# ESP32_S3.net
KiCad netlist of a schematic drawn in Altium Designer
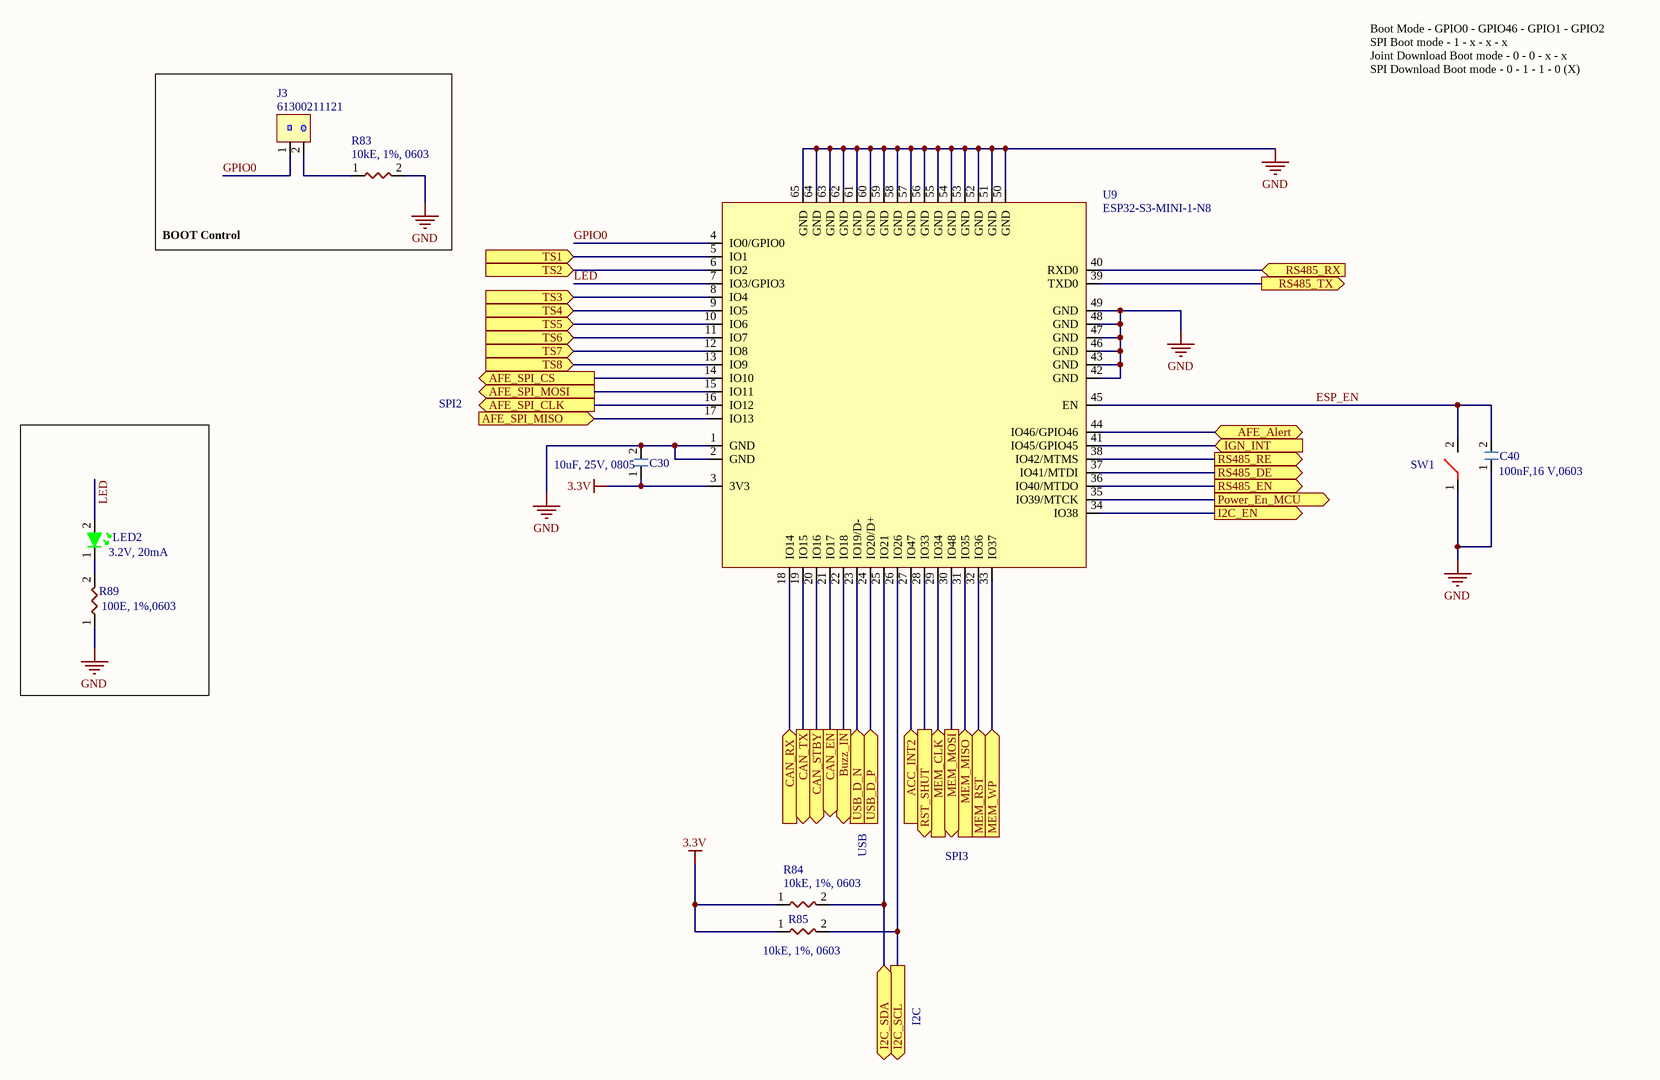
[diagram p0: ESP32_S3.SchDoc]

(export (version "E")
  (design (tool "Eeschema 10.0.6"))
  (components
    (comp (ref "C30")
      (value "GRM21BZ71E106KE15L")
      (footprint "BMS_V2.1_Adv:CAPC2012X13N 0805")
      (description "Multilayer Ceramic Capacitor, 10 uF, 25V, ±10%,  X7R 0805 (2012 Metric)")
      (fields
        (field (name "MANUFACTURER") "Murata")
        (field (name "TOLERANCE") "10%")
        (field (name "VALUE DISPLAY") "10uF, 25V, 0805")
      )
      (libsource (lib "BMS_V2.1_Adv") (part "Cap_GRM21BZ71E106KE15L"))
    )
    (comp (ref "C40")
      (value "CC0603KRX7R7BB104")
      (footprint "BMS_V2.1_Adv:CAPC1608X05N 0603")
      (description "Multilayer Ceramic Capacitor, 100 nF, 16V, ±10%,  X7R 0603 [1608 Metric]")
      (fields
        (field (name "MANUFACTURER") "Yageo")
        (field (name "TOLERANCE") "10%")
        (field (name "VALUE DISPLAY") "100nF,16 V,0603")
      )
      (libsource (lib "BMS_V2.1_Adv") (part "Cap_CC0603KRX7R7BB104"))
    )
    (comp (ref "J3")
      (value "61300211121")
      (footprint "BMS_V2.1_Adv:Con_61300211121")
      (description "Connector Header Through Hole 2 position 0.100\" (2.54mm)")
      (fields
        (field (name "CRIMP PART NUMBER") "609002115121")
        (field (name "MANUFACTURER") "Wurth Electronik")
      )
      (libsource (lib "BMS_V2.1_Adv") (part "Con_61300211121"))
    )
    (comp (ref "LED2")
      (value "150060GS75000")
      (footprint "BMS_V2.1_Adv:DIOC1610X08N LED")
      (description "Green 520nm LED Indication - Discrete 3.2V 0603 (1608 Metric)")
      (fields
        (field (name "MANUFACTURER") "Wurth Electronik")
        (field (name "VALUE DISPLAY") "3.2V, 20mA")
        (field (name "POWER") "105mW")
      )
      (libsource (lib "BMS_V2.1_Adv") (part "LED_150060GS75000"))
    )
    (comp (ref "R83")
      (value "CRCW060310K0FKEA")
      (footprint "BMS_V2.1_Adv:RESC1608X05N 0603")
      (description "SMD Chip Resistor, 10 kOhm,±1%, 100 mW, 0603 [1608 Metric], Thick Film, General Purpose")
      (fields
        (field (name "MANUFACTURER") "Vishay Dale")
        (field (name "POWER") "1/10W")
        (field (name "VALUE DISPLAY") "10kE, 1%, 0603")
      )
      (libsource (lib "BMS_V2.1_Adv") (part "Res_CRCW060310K0FKEA"))
    )
    (comp (ref "R84")
      (value "CRCW060310K0FKEA")
      (footprint "BMS_V2.1_Adv:RESC1608X05N 0603")
      (description "SMD Chip Resistor, 10 kOhm,±1%, 100 mW, 0603 [1608 Metric], Thick Film, General Purpose")
      (fields
        (field (name "MANUFACTURER") "Vishay Dale")
        (field (name "POWER") "1/10W")
        (field (name "VALUE DISPLAY") "10kE, 1%, 0603")
      )
      (libsource (lib "BMS_V2.1_Adv") (part "Res_CRCW060310K0FKEA"))
    )
    (comp (ref "R85")
      (value "CRCW060310K0FKEA")
      (footprint "BMS_V2.1_Adv:RESC1608X05N 0603")
      (description "SMD Chip Resistor, 10 kOhm,±1%, 100 mW, 0603 [1608 Metric], Thick Film, General Purpose")
      (fields
        (field (name "MANUFACTURER") "Vishay Dale")
        (field (name "POWER") "1/10W")
        (field (name "VALUE DISPLAY") "10kE, 1%, 0603")
      )
      (libsource (lib "BMS_V2.1_Adv") (part "Res_CRCW060310K0FKEA"))
    )
    (comp (ref "R89")
      (value "AF0603FR-07100RL")
      (footprint "BMS_V2.1_Adv:RESC1608X05N 0603")
      (fields
        (field (name "TOLERANCE") "1%")
        (field (name "MANUFACTURER") "Yageo")
        (field (name "POWER") "1/10W")
        (field (name "VALUE DISPLAY") "100E, 1%,0603")
      )
      (libsource (lib "BMS_V2.1_Adv") (part "Res_AF0603FR-07100RL"))
    )
    (comp (ref "SW1")
      (value "TL3305AF260QG")
      (footprint "BMS_V2.1_Adv:SW_TL3305AF260QG")
      (description "SWITCH TACTILE SPST-NO 0.05A 12V")
      (fields (field (name "MANUFACTURER") "E Switch"))
      (libsource (lib "BMS_V2.1_Adv") (part "Sw_TL3305AF260QG"))
    )
    (comp (ref "U9")
      (value "ESP32-S3-MINI-1-N8")
      (footprint "BMS_V2.1_Adv:ESP32-S3_MINI")
      (description "Multiprotocol Modules SMD module, ESP32-S3FN8, 8 MB SPI flash, PCB antenna")
      (fields (field (name "MANUFACTURER") "Espressif"))
      (libsource (lib "BMS_V2.1_Adv") (part "IC_ESP32-S3-MINI-1-N8"))
    )
  )
  (nets
    (net (code "1") (name "/ACC_INT2") (class "Default")
      (node (ref "U9") (pin "27") (pinfunction "IO47_27") (pintype "passive"))
    )
    (net (code "2") (name "/AFE_Alert") (class "Default")
      (node (ref "U9") (pin "44") (pinfunction "IO46/GPIO46_44") (pintype "passive"))
    )
    (net (code "3") (name "/AFE_SPI_CLK") (class "Default")
      (node (ref "U9") (pin "16") (pinfunction "IO12_16") (pintype "passive"))
    )
    (net (code "4") (name "/AFE_SPI_CS") (class "Default")
      (node (ref "U9") (pin "14") (pinfunction "IO10_14") (pintype "passive"))
    )
    (net (code "5") (name "/AFE_SPI_MISO") (class "Default")
      (node (ref "U9") (pin "17") (pinfunction "IO13_17") (pintype "passive"))
    )
    (net (code "6") (name "/AFE_SPI_MOSI") (class "Default")
      (node (ref "U9") (pin "15") (pinfunction "IO11_15") (pintype "passive"))
    )
    (net (code "7") (name "/Buzz_IN") (class "Default")
      (node (ref "U9") (pin "22") (pinfunction "IO18_22") (pintype "passive"))
    )
    (net (code "8") (name "/CAN_EN") (class "Default")
      (node (ref "U9") (pin "21") (pinfunction "IO17_21") (pintype "passive"))
    )
    (net (code "9") (name "/CAN_RX") (class "Default")
      (node (ref "U9") (pin "18") (pinfunction "IO14_18") (pintype "passive"))
    )
    (net (code "10") (name "/CAN_STBY") (class "Default")
      (node (ref "U9") (pin "20") (pinfunction "IO16_20") (pintype "passive"))
    )
    (net (code "11") (name "/CAN_TX") (class "Default")
      (node (ref "U9") (pin "19") (pinfunction "IO15_19") (pintype "passive"))
    )
    (net (code "12") (name "/ESP_EN") (class "Default")
      (node (ref "C40") (pin "2") (pinfunction "2_2") (pintype "passive"))
      (node (ref "SW1") (pin "2") (pinfunction "2_2") (pintype "passive"))
      (node (ref "U9") (pin "45") (pinfunction "EN_45") (pintype "passive"))
    )
    (net (code "13") (name "/GPIO0") (class "Default")
      (node (ref "J3") (pin "1") (pinfunction "1_1") (pintype "passive"))
      (node (ref "U9") (pin "4") (pinfunction "IO0/GPIO0_4") (pintype "passive"))
    )
    (net (code "14") (name "/I2C_EN") (class "Default")
      (node (ref "U9") (pin "34") (pinfunction "IO38_34") (pintype "passive"))
    )
    (net (code "15") (name "/I2C_SCL") (class "Default")
      (node (ref "R85") (pin "2") (pinfunction "2_2") (pintype "passive"))
      (node (ref "U9") (pin "26") (pinfunction "IO26_26") (pintype "passive"))
    )
    (net (code "16") (name "/I2C_SDA") (class "Default")
      (node (ref "R84") (pin "2") (pinfunction "2_2") (pintype "passive"))
      (node (ref "U9") (pin "25") (pinfunction "IO21_25") (pintype "passive"))
    )
    (net (code "17") (name "/IGN_INT") (class "Default")
      (node (ref "U9") (pin "41") (pinfunction "IO45/GPIO45_41") (pintype "passive"))
    )
    (net (code "18") (name "/LED") (class "Default")
      (node (ref "LED2") (pin "2") (pinfunction "Anode_2") (pintype "passive"))
      (node (ref "U9") (pin "7") (pinfunction "IO3/GPIO3_7") (pintype "passive"))
    )
    (net (code "19") (name "/MEM_CLK") (class "Default")
      (node (ref "U9") (pin "29") (pinfunction "IO34_29") (pintype "passive"))
    )
    (net (code "20") (name "/MEM_MISO") (class "Default")
      (node (ref "U9") (pin "31") (pinfunction "IO35_31") (pintype "passive"))
    )
    (net (code "21") (name "/MEM_MOSI") (class "Default")
      (node (ref "U9") (pin "30") (pinfunction "IO48_30") (pintype "passive"))
    )
    (net (code "22") (name "/MEM_RST") (class "Default")
      (node (ref "U9") (pin "32") (pinfunction "IO36_32") (pintype "passive"))
    )
    (net (code "23") (name "/MEM_WP") (class "Default")
      (node (ref "U9") (pin "33") (pinfunction "IO37_33") (pintype "passive"))
    )
    (net (code "24") (name "/Power_En_MCU") (class "Default")
      (node (ref "U9") (pin "35") (pinfunction "IO39/MTCK_35") (pintype "passive"))
    )
    (net (code "25") (name "/RS485_DE") (class "Default")
      (node (ref "U9") (pin "37") (pinfunction "IO41/MTDI_37") (pintype "passive"))
    )
    (net (code "26") (name "/RS485_EN") (class "Default")
      (node (ref "U9") (pin "36") (pinfunction "IO40/MTDO_36") (pintype "passive"))
    )
    (net (code "27") (name "/RS485_RE") (class "Default")
      (node (ref "U9") (pin "38") (pinfunction "IO42/MTMS_38") (pintype "passive"))
    )
    (net (code "28") (name "/RS485_RX") (class "Default")
      (node (ref "U9") (pin "40") (pinfunction "RXD0_40") (pintype "passive"))
    )
    (net (code "29") (name "/RS485_TX") (class "Default")
      (node (ref "U9") (pin "39") (pinfunction "TXD0_39") (pintype "passive"))
    )
    (net (code "30") (name "/RST_SHUT") (class "Default")
      (node (ref "U9") (pin "28") (pinfunction "IO33_28") (pintype "passive"))
    )
    (net (code "31") (name "/TS1") (class "Default")
      (node (ref "U9") (pin "5") (pinfunction "IO1_5") (pintype "passive"))
    )
    (net (code "32") (name "/TS2") (class "Default")
      (node (ref "U9") (pin "6") (pinfunction "IO2_6") (pintype "passive"))
    )
    (net (code "33") (name "/TS3") (class "Default")
      (node (ref "U9") (pin "8") (pinfunction "IO4_8") (pintype "passive"))
    )
    (net (code "34") (name "/TS4") (class "Default")
      (node (ref "U9") (pin "9") (pinfunction "IO5_9") (pintype "passive"))
    )
    (net (code "35") (name "/TS5") (class "Default")
      (node (ref "U9") (pin "10") (pinfunction "IO6_10") (pintype "passive"))
    )
    (net (code "36") (name "/TS6") (class "Default")
      (node (ref "U9") (pin "11") (pinfunction "IO7_11") (pintype "passive"))
    )
    (net (code "37") (name "/TS7") (class "Default")
      (node (ref "U9") (pin "12") (pinfunction "IO8_12") (pintype "passive"))
    )
    (net (code "38") (name "/TS8") (class "Default")
      (node (ref "U9") (pin "13") (pinfunction "IO9_13") (pintype "passive"))
    )
    (net (code "39") (name "/USB_D_N") (class "Default")
      (node (ref "U9") (pin "23") (pinfunction "IO19/D-_23") (pintype "passive"))
    )
    (net (code "40") (name "/USB_D_P") (class "Default")
      (node (ref "U9") (pin "24") (pinfunction "IO20/D+_24") (pintype "passive"))
    )
    (net (code "41") (name "3.3V") (class "Default")
      (node (ref "C30") (pin "1") (pinfunction "1_1") (pintype "passive"))
      (node (ref "R84") (pin "1") (pinfunction "1_1") (pintype "passive"))
      (node (ref "R85") (pin "1") (pinfunction "1_1") (pintype "passive"))
      (node (ref "U9") (pin "3") (pinfunction "3V3_3") (pintype "passive"))
    )
    (net (code "42") (name "GND") (class "Default")
      (node (ref "C30") (pin "2") (pinfunction "2_2") (pintype "passive"))
      (node (ref "C40") (pin "1") (pinfunction "1_1") (pintype "passive"))
      (node (ref "R83") (pin "2") (pinfunction "2_2") (pintype "passive"))
      (node (ref "R89") (pin "1") (pinfunction "1_1") (pintype "passive"))
      (node (ref "SW1") (pin "1") (pinfunction "1_1") (pintype "passive"))
      (node (ref "U9") (pin "1") (pinfunction "GND_1") (pintype "passive"))
      (node (ref "U9") (pin "2") (pinfunction "GND_2") (pintype "passive"))
      (node (ref "U9") (pin "42") (pinfunction "GND_42") (pintype "passive"))
      (node (ref "U9") (pin "43") (pinfunction "GND_43") (pintype "passive"))
      (node (ref "U9") (pin "46") (pinfunction "GND_46") (pintype "passive"))
      (node (ref "U9") (pin "47") (pinfunction "GND_47") (pintype "passive"))
      (node (ref "U9") (pin "48") (pinfunction "GND_48") (pintype "passive"))
      (node (ref "U9") (pin "49") (pinfunction "GND_49") (pintype "passive"))
      (node (ref "U9") (pin "50") (pinfunction "GND_50") (pintype "passive"))
      (node (ref "U9") (pin "51") (pinfunction "GND_51") (pintype "passive"))
      (node (ref "U9") (pin "52") (pinfunction "GND_52") (pintype "passive"))
      (node (ref "U9") (pin "53") (pinfunction "GND_53") (pintype "passive"))
      (node (ref "U9") (pin "54") (pinfunction "GND_54") (pintype "passive"))
      (node (ref "U9") (pin "55") (pinfunction "GND_55") (pintype "passive"))
      (node (ref "U9") (pin "56") (pinfunction "GND_56") (pintype "passive"))
      (node (ref "U9") (pin "57") (pinfunction "GND_57") (pintype "passive"))
      (node (ref "U9") (pin "58") (pinfunction "GND_58") (pintype "passive"))
      (node (ref "U9") (pin "59") (pinfunction "GND_59") (pintype "passive"))
      (node (ref "U9") (pin "60") (pinfunction "GND_60") (pintype "passive"))
      (node (ref "U9") (pin "61") (pinfunction "GND_61") (pintype "passive"))
      (node (ref "U9") (pin "62") (pinfunction "GND_62") (pintype "passive"))
      (node (ref "U9") (pin "63") (pinfunction "GND_63") (pintype "passive"))
      (node (ref "U9") (pin "64") (pinfunction "GND_64") (pintype "passive"))
      (node (ref "U9") (pin "65") (pinfunction "GND_65") (pintype "passive"))
    )
    (net (code "43") (name "Net-(J3-Pad2)") (class "Default")
      (node (ref "J3") (pin "2") (pinfunction "2_2") (pintype "passive"))
      (node (ref "R83") (pin "1") (pinfunction "1_1") (pintype "passive"))
    )
    (net (code "44") (name "Net-(LED2-Cathode)") (class "Default")
      (node (ref "LED2") (pin "1") (pinfunction "Cathode_1") (pintype "passive"))
      (node (ref "R89") (pin "2") (pinfunction "2_2") (pintype "passive"))
    )
  )
)
